# Keyfinder_Power.net
KiCad netlist of a schematic drawn in Altium Designer
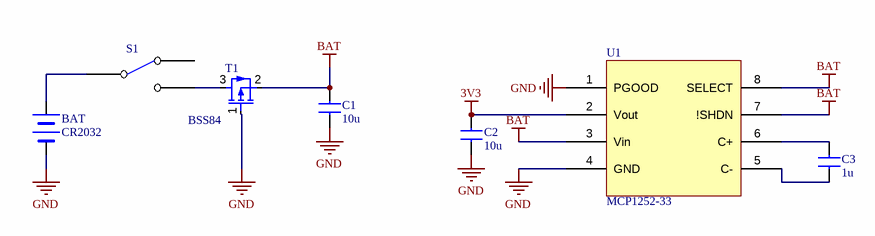
[diagram p0: Keyfinder_Power.SchDoc]

(export (version "E")
  (design (tool "Eeschema 10.0.6"))
  (components
    (comp (ref "BAT")
      (value "CR2032")
      (footprint "Bat_case")
      (libsource (lib "DEVICE_HSLU") (part "BATTERY"))
    )
    (comp (ref "C1")
      (value "10u")
      (footprint "0805_C")
      (description "Normaler Kondensator")
      (libsource (lib "MainBoard") (part "C?"))
    )
    (comp (ref "C2")
      (value "10u")
      (footprint "0805_C")
      (description "Normaler Kondensator")
      (libsource (lib "MainBoard") (part "C?"))
    )
    (comp (ref "C3")
      (value "1u")
      (footprint "0805_C")
      (description "Normaler Kondensator")
      (libsource (lib "MainBoard") (part "C?"))
    )
    (comp (ref "S1")
      (value "SW SPDT")
      (footprint "SW_MCLSS22")
      (libsource (lib "DEVICE_HSLU") (part "SW SPDT"))
    )
    (comp (ref "T1")
      (value "BSS84")
      (footprint "SOT23-3")
      (description "MOSFET-P 1G,2D,3S (Diode)")
      (libsource (lib "Sch_Lib") (part "MOSFET-P 1G,2D,3S (Diode)"))
    )
    (comp (ref "U1") (value "MCP1252-33") (footprint "MSOP8") (libsource (lib "MainBoard") (part "VOLTREG")))
  )
  (nets
    (net (code "1") (name "3V3") (class "Default")
      (node (ref "C2") (pin "2") (pinfunction "2_2") (pintype "passive"))
      (node (ref "U1") (pin "2") (pinfunction "Vout_2") (pintype "passive"))
    )
    (net (code "2") (name "BAT") (class "Default")
      (node (ref "C1") (pin "2") (pinfunction "2_2") (pintype "passive"))
      (node (ref "T1") (pin "2") (pinfunction "S_2") (pintype "passive"))
      (node (ref "U1") (pin "3") (pinfunction "Vin_3") (pintype "passive"))
      (node (ref "U1") (pin "7") (pinfunction "!SHDN_7") (pintype "passive"))
      (node (ref "U1") (pin "8") (pinfunction "SELECT_8") (pintype "passive"))
    )
    (net (code "3") (name "GND") (class "Default")
      (node (ref "BAT") (pin "2") (pintype "passive"))
      (node (ref "C1") (pin "1") (pinfunction "1_1") (pintype "passive"))
      (node (ref "C2") (pin "1") (pinfunction "1_1") (pintype "passive"))
      (node (ref "T1") (pin "1") (pinfunction "G_1") (pintype "passive"))
      (node (ref "U1") (pin "1") (pinfunction "PGOOD_1") (pintype "passive"))
      (node (ref "U1") (pin "4") (pinfunction "GND_4") (pintype "passive"))
    )
    (net (code "4") (name "Net-(S1-COMMON)") (class "Default")
      (node (ref "BAT") (pin "1") (pintype "passive"))
      (node (ref "S1") (pin "2") (pinfunction "COMMON_2") (pintype "passive"))
    )
    (net (code "5") (name "Net-(S1-NO)") (class "Default")
      (node (ref "S1") (pin "3") (pinfunction "NO_3") (pintype "passive"))
      (node (ref "T1") (pin "3") (pinfunction "D_3") (pintype "passive"))
    )
    (net (code "6") (name "Net-(U1-C+)") (class "Default")
      (node (ref "C3") (pin "2") (pinfunction "2_2") (pintype "passive"))
      (node (ref "U1") (pin "6") (pinfunction "C+_6") (pintype "passive"))
    )
    (net (code "7") (name "Net-(U1-C-)") (class "Default")
      (node (ref "C3") (pin "1") (pinfunction "1_1") (pintype "passive"))
      (node (ref "U1") (pin "5") (pinfunction "C-_5") (pintype "passive"))
    )
    (net (code "8") (name "unconnected-(S1-NC-Pad1)") (class "Default")
      (node (ref "S1") (pin "1") (pinfunction "NC_1") (pintype "passive"))
    )
  )
)
